# MiniFrontplane.net
KiCad netlist of a schematic drawn in EAGLE
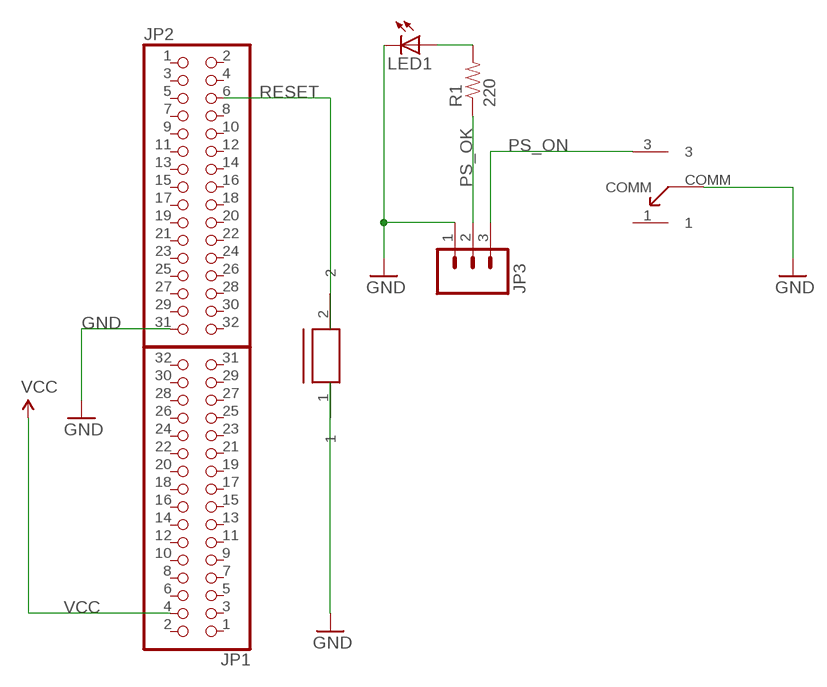
[diagram p0: schematic, sheet 1]

(export (version "E")
  (design (tool "Eeschema 10.0.6"))
  (components
    (comp (ref "JP1")
      (value "PINHD-2X16")
      (footprint "eagle-import:2X16")
      (libsource (lib "eagle-import") (part "PINHD-2X16"))
    )
    (comp (ref "JP2")
      (value "PINHD-2X16")
      (footprint "eagle-import:2X16")
      (libsource (lib "eagle-import") (part "PINHD-2X16"))
    )
    (comp (ref "JP3")
      (value "M03LONGPADS")
      (footprint "eagle-import:1X03_LONGPADS")
      (libsource (lib "eagle-import") (part "M03LONGPADS"))
    )
    (comp (ref "LED1")
      (value "LED5MM")
      (footprint "eagle-import:LED5MM")
      (libsource (lib "eagle-import") (part "LED5MM"))
    )
    (comp (ref "R1")
      (value "220")
      (footprint "eagle-import:AXIAL-0.3-KIT")
      (libsource (lib "eagle-import") (part "RESISTORKIT"))
    )
    (comp (ref "U$1")
      (value "7101")
      (footprint "eagle-import:7101SYCQE")
      (libsource (lib "eagle-import") (part "7101"))
    )
    (comp (ref "U$2")
      (value "TP11")
      (footprint "eagle-import:TP11")
      (libsource (lib "eagle-import") (part "TP11"))
    )
  )
  (nets
    (net (code "1") (name "/PS_OK") (class "Default")
      (node (ref "JP3") (pin "2") (pinfunction "2_2") (pintype "passive"))
      (node (ref "R1") (pin "P$1") (pinfunction "1_P$1") (pintype "passive"))
    )
    (net (code "2") (name "/PS_ON") (class "Default")
      (node (ref "JP3") (pin "3") (pinfunction "3_3") (pintype "passive"))
      (node (ref "U$1") (pin "3") (pinfunction "3_3") (pintype "bidirectional"))
    )
    (net (code "3") (name "/RESET") (class "Default")
      (node (ref "JP2") (pin "6") (pinfunction "6_6") (pintype "passive"))
      (node (ref "U$2") (pin "2") (pinfunction "2_2") (pintype "bidirectional"))
    )
    (net (code "4") (name "GND") (class "Default")
      (node (ref "JP2") (pin "31") (pinfunction "31_31") (pintype "passive"))
      (node (ref "JP3") (pin "1") (pinfunction "1_1") (pintype "passive"))
      (node (ref "LED1") (pin "K") (pinfunction "C_K") (pintype "passive"))
      (node (ref "U$1") (pin "COMM") (pinfunction "COMM_COMM") (pintype "bidirectional"))
      (node (ref "U$2") (pin "1") (pinfunction "1_1") (pintype "bidirectional"))
    )
    (net (code "5") (name "Net-(R1-2)") (class "Default")
      (node (ref "LED1") (pin "A") (pinfunction "A_A") (pintype "passive"))
      (node (ref "R1") (pin "P$2") (pinfunction "2_P$2") (pintype "passive"))
    )
    (net (code "6") (name "VCC") (class "Default")
      (node (ref "JP1") (pin "4") (pinfunction "4_4") (pintype "passive"))
    )
    (net (code "7") (name "unconnected-(JP1-Pad1)") (class "Default")
      (node (ref "JP1") (pin "1") (pinfunction "1_1") (pintype "passive"))
    )
    (net (code "8") (name "unconnected-(JP1-Pad2)") (class "Default")
      (node (ref "JP1") (pin "2") (pinfunction "2_2") (pintype "passive"))
    )
    (net (code "9") (name "unconnected-(JP1-Pad3)") (class "Default")
      (node (ref "JP1") (pin "3") (pinfunction "3_3") (pintype "passive"))
    )
    (net (code "10") (name "unconnected-(JP1-Pad5)") (class "Default")
      (node (ref "JP1") (pin "5") (pinfunction "5_5") (pintype "passive"))
    )
    (net (code "11") (name "unconnected-(JP1-Pad6)") (class "Default")
      (node (ref "JP1") (pin "6") (pinfunction "6_6") (pintype "passive"))
    )
    (net (code "12") (name "unconnected-(JP1-Pad7)") (class "Default")
      (node (ref "JP1") (pin "7") (pinfunction "7_7") (pintype "passive"))
    )
    (net (code "13") (name "unconnected-(JP1-Pad8)") (class "Default")
      (node (ref "JP1") (pin "8") (pinfunction "8_8") (pintype "passive"))
    )
    (net (code "14") (name "unconnected-(JP1-Pad9)") (class "Default")
      (node (ref "JP1") (pin "9") (pinfunction "9_9") (pintype "passive"))
    )
    (net (code "15") (name "unconnected-(JP1-Pad10)") (class "Default")
      (node (ref "JP1") (pin "10") (pinfunction "10_10") (pintype "passive"))
    )
    (net (code "16") (name "unconnected-(JP1-Pad11)") (class "Default")
      (node (ref "JP1") (pin "11") (pinfunction "11_11") (pintype "passive"))
    )
    (net (code "17") (name "unconnected-(JP1-Pad12)") (class "Default")
      (node (ref "JP1") (pin "12") (pinfunction "12_12") (pintype "passive"))
    )
    (net (code "18") (name "unconnected-(JP1-Pad13)") (class "Default")
      (node (ref "JP1") (pin "13") (pinfunction "13_13") (pintype "passive"))
    )
    (net (code "19") (name "unconnected-(JP1-Pad14)") (class "Default")
      (node (ref "JP1") (pin "14") (pinfunction "14_14") (pintype "passive"))
    )
    (net (code "20") (name "unconnected-(JP1-Pad15)") (class "Default")
      (node (ref "JP1") (pin "15") (pinfunction "15_15") (pintype "passive"))
    )
    (net (code "21") (name "unconnected-(JP1-Pad16)") (class "Default")
      (node (ref "JP1") (pin "16") (pinfunction "16_16") (pintype "passive"))
    )
    (net (code "22") (name "unconnected-(JP1-Pad17)") (class "Default")
      (node (ref "JP1") (pin "17") (pinfunction "17_17") (pintype "passive"))
    )
    (net (code "23") (name "unconnected-(JP1-Pad18)") (class "Default")
      (node (ref "JP1") (pin "18") (pinfunction "18_18") (pintype "passive"))
    )
    (net (code "24") (name "unconnected-(JP1-Pad19)") (class "Default")
      (node (ref "JP1") (pin "19") (pinfunction "19_19") (pintype "passive"))
    )
    (net (code "25") (name "unconnected-(JP1-Pad20)") (class "Default")
      (node (ref "JP1") (pin "20") (pinfunction "20_20") (pintype "passive"))
    )
    (net (code "26") (name "unconnected-(JP1-Pad21)") (class "Default")
      (node (ref "JP1") (pin "21") (pinfunction "21_21") (pintype "passive"))
    )
    (net (code "27") (name "unconnected-(JP1-Pad22)") (class "Default")
      (node (ref "JP1") (pin "22") (pinfunction "22_22") (pintype "passive"))
    )
    (net (code "28") (name "unconnected-(JP1-Pad23)") (class "Default")
      (node (ref "JP1") (pin "23") (pinfunction "23_23") (pintype "passive"))
    )
    (net (code "29") (name "unconnected-(JP1-Pad24)") (class "Default")
      (node (ref "JP1") (pin "24") (pinfunction "24_24") (pintype "passive"))
    )
    (net (code "30") (name "unconnected-(JP1-Pad25)") (class "Default")
      (node (ref "JP1") (pin "25") (pinfunction "25_25") (pintype "passive"))
    )
    (net (code "31") (name "unconnected-(JP1-Pad26)") (class "Default")
      (node (ref "JP1") (pin "26") (pinfunction "26_26") (pintype "passive"))
    )
    (net (code "32") (name "unconnected-(JP1-Pad27)") (class "Default")
      (node (ref "JP1") (pin "27") (pinfunction "27_27") (pintype "passive"))
    )
    (net (code "33") (name "unconnected-(JP1-Pad28)") (class "Default")
      (node (ref "JP1") (pin "28") (pinfunction "28_28") (pintype "passive"))
    )
    (net (code "34") (name "unconnected-(JP1-Pad29)") (class "Default")
      (node (ref "JP1") (pin "29") (pinfunction "29_29") (pintype "passive"))
    )
    (net (code "35") (name "unconnected-(JP1-Pad30)") (class "Default")
      (node (ref "JP1") (pin "30") (pinfunction "30_30") (pintype "passive"))
    )
    (net (code "36") (name "unconnected-(JP1-Pad31)") (class "Default")
      (node (ref "JP1") (pin "31") (pinfunction "31_31") (pintype "passive"))
    )
    (net (code "37") (name "unconnected-(JP1-Pad32)") (class "Default")
      (node (ref "JP1") (pin "32") (pinfunction "32_32") (pintype "passive"))
    )
    (net (code "38") (name "unconnected-(JP2-Pad1)") (class "Default")
      (node (ref "JP2") (pin "1") (pinfunction "1_1") (pintype "passive"))
    )
    (net (code "39") (name "unconnected-(JP2-Pad2)") (class "Default")
      (node (ref "JP2") (pin "2") (pinfunction "2_2") (pintype "passive"))
    )
    (net (code "40") (name "unconnected-(JP2-Pad3)") (class "Default")
      (node (ref "JP2") (pin "3") (pinfunction "3_3") (pintype "passive"))
    )
    (net (code "41") (name "unconnected-(JP2-Pad4)") (class "Default")
      (node (ref "JP2") (pin "4") (pinfunction "4_4") (pintype "passive"))
    )
    (net (code "42") (name "unconnected-(JP2-Pad5)") (class "Default")
      (node (ref "JP2") (pin "5") (pinfunction "5_5") (pintype "passive"))
    )
    (net (code "43") (name "unconnected-(JP2-Pad7)") (class "Default")
      (node (ref "JP2") (pin "7") (pinfunction "7_7") (pintype "passive"))
    )
    (net (code "44") (name "unconnected-(JP2-Pad8)") (class "Default")
      (node (ref "JP2") (pin "8") (pinfunction "8_8") (pintype "passive"))
    )
    (net (code "45") (name "unconnected-(JP2-Pad9)") (class "Default")
      (node (ref "JP2") (pin "9") (pinfunction "9_9") (pintype "passive"))
    )
    (net (code "46") (name "unconnected-(JP2-Pad10)") (class "Default")
      (node (ref "JP2") (pin "10") (pinfunction "10_10") (pintype "passive"))
    )
    (net (code "47") (name "unconnected-(JP2-Pad11)") (class "Default")
      (node (ref "JP2") (pin "11") (pinfunction "11_11") (pintype "passive"))
    )
    (net (code "48") (name "unconnected-(JP2-Pad12)") (class "Default")
      (node (ref "JP2") (pin "12") (pinfunction "12_12") (pintype "passive"))
    )
    (net (code "49") (name "unconnected-(JP2-Pad13)") (class "Default")
      (node (ref "JP2") (pin "13") (pinfunction "13_13") (pintype "passive"))
    )
    (net (code "50") (name "unconnected-(JP2-Pad14)") (class "Default")
      (node (ref "JP2") (pin "14") (pinfunction "14_14") (pintype "passive"))
    )
    (net (code "51") (name "unconnected-(JP2-Pad15)") (class "Default")
      (node (ref "JP2") (pin "15") (pinfunction "15_15") (pintype "passive"))
    )
    (net (code "52") (name "unconnected-(JP2-Pad16)") (class "Default")
      (node (ref "JP2") (pin "16") (pinfunction "16_16") (pintype "passive"))
    )
    (net (code "53") (name "unconnected-(JP2-Pad17)") (class "Default")
      (node (ref "JP2") (pin "17") (pinfunction "17_17") (pintype "passive"))
    )
    (net (code "54") (name "unconnected-(JP2-Pad18)") (class "Default")
      (node (ref "JP2") (pin "18") (pinfunction "18_18") (pintype "passive"))
    )
    (net (code "55") (name "unconnected-(JP2-Pad19)") (class "Default")
      (node (ref "JP2") (pin "19") (pinfunction "19_19") (pintype "passive"))
    )
    (net (code "56") (name "unconnected-(JP2-Pad20)") (class "Default")
      (node (ref "JP2") (pin "20") (pinfunction "20_20") (pintype "passive"))
    )
    (net (code "57") (name "unconnected-(JP2-Pad21)") (class "Default")
      (node (ref "JP2") (pin "21") (pinfunction "21_21") (pintype "passive"))
    )
    (net (code "58") (name "unconnected-(JP2-Pad22)") (class "Default")
      (node (ref "JP2") (pin "22") (pinfunction "22_22") (pintype "passive"))
    )
    (net (code "59") (name "unconnected-(JP2-Pad23)") (class "Default")
      (node (ref "JP2") (pin "23") (pinfunction "23_23") (pintype "passive"))
    )
    (net (code "60") (name "unconnected-(JP2-Pad24)") (class "Default")
      (node (ref "JP2") (pin "24") (pinfunction "24_24") (pintype "passive"))
    )
    (net (code "61") (name "unconnected-(JP2-Pad25)") (class "Default")
      (node (ref "JP2") (pin "25") (pinfunction "25_25") (pintype "passive"))
    )
    (net (code "62") (name "unconnected-(JP2-Pad26)") (class "Default")
      (node (ref "JP2") (pin "26") (pinfunction "26_26") (pintype "passive"))
    )
    (net (code "63") (name "unconnected-(JP2-Pad27)") (class "Default")
      (node (ref "JP2") (pin "27") (pinfunction "27_27") (pintype "passive"))
    )
    (net (code "64") (name "unconnected-(JP2-Pad28)") (class "Default")
      (node (ref "JP2") (pin "28") (pinfunction "28_28") (pintype "passive"))
    )
    (net (code "65") (name "unconnected-(JP2-Pad29)") (class "Default")
      (node (ref "JP2") (pin "29") (pinfunction "29_29") (pintype "passive"))
    )
    (net (code "66") (name "unconnected-(JP2-Pad30)") (class "Default")
      (node (ref "JP2") (pin "30") (pinfunction "30_30") (pintype "passive"))
    )
    (net (code "67") (name "unconnected-(JP2-Pad32)") (class "Default")
      (node (ref "JP2") (pin "32") (pinfunction "32_32") (pintype "passive"))
    )
    (net (code "68") (name "unconnected-(U$1-Pad1)") (class "Default")
      (node (ref "U$1") (pin "1") (pinfunction "1_1") (pintype "bidirectional"))
    )
  )
)
